# Fri3D_IRA_ESP32.net
KiCad netlist of a schematic drawn in Altium Designer
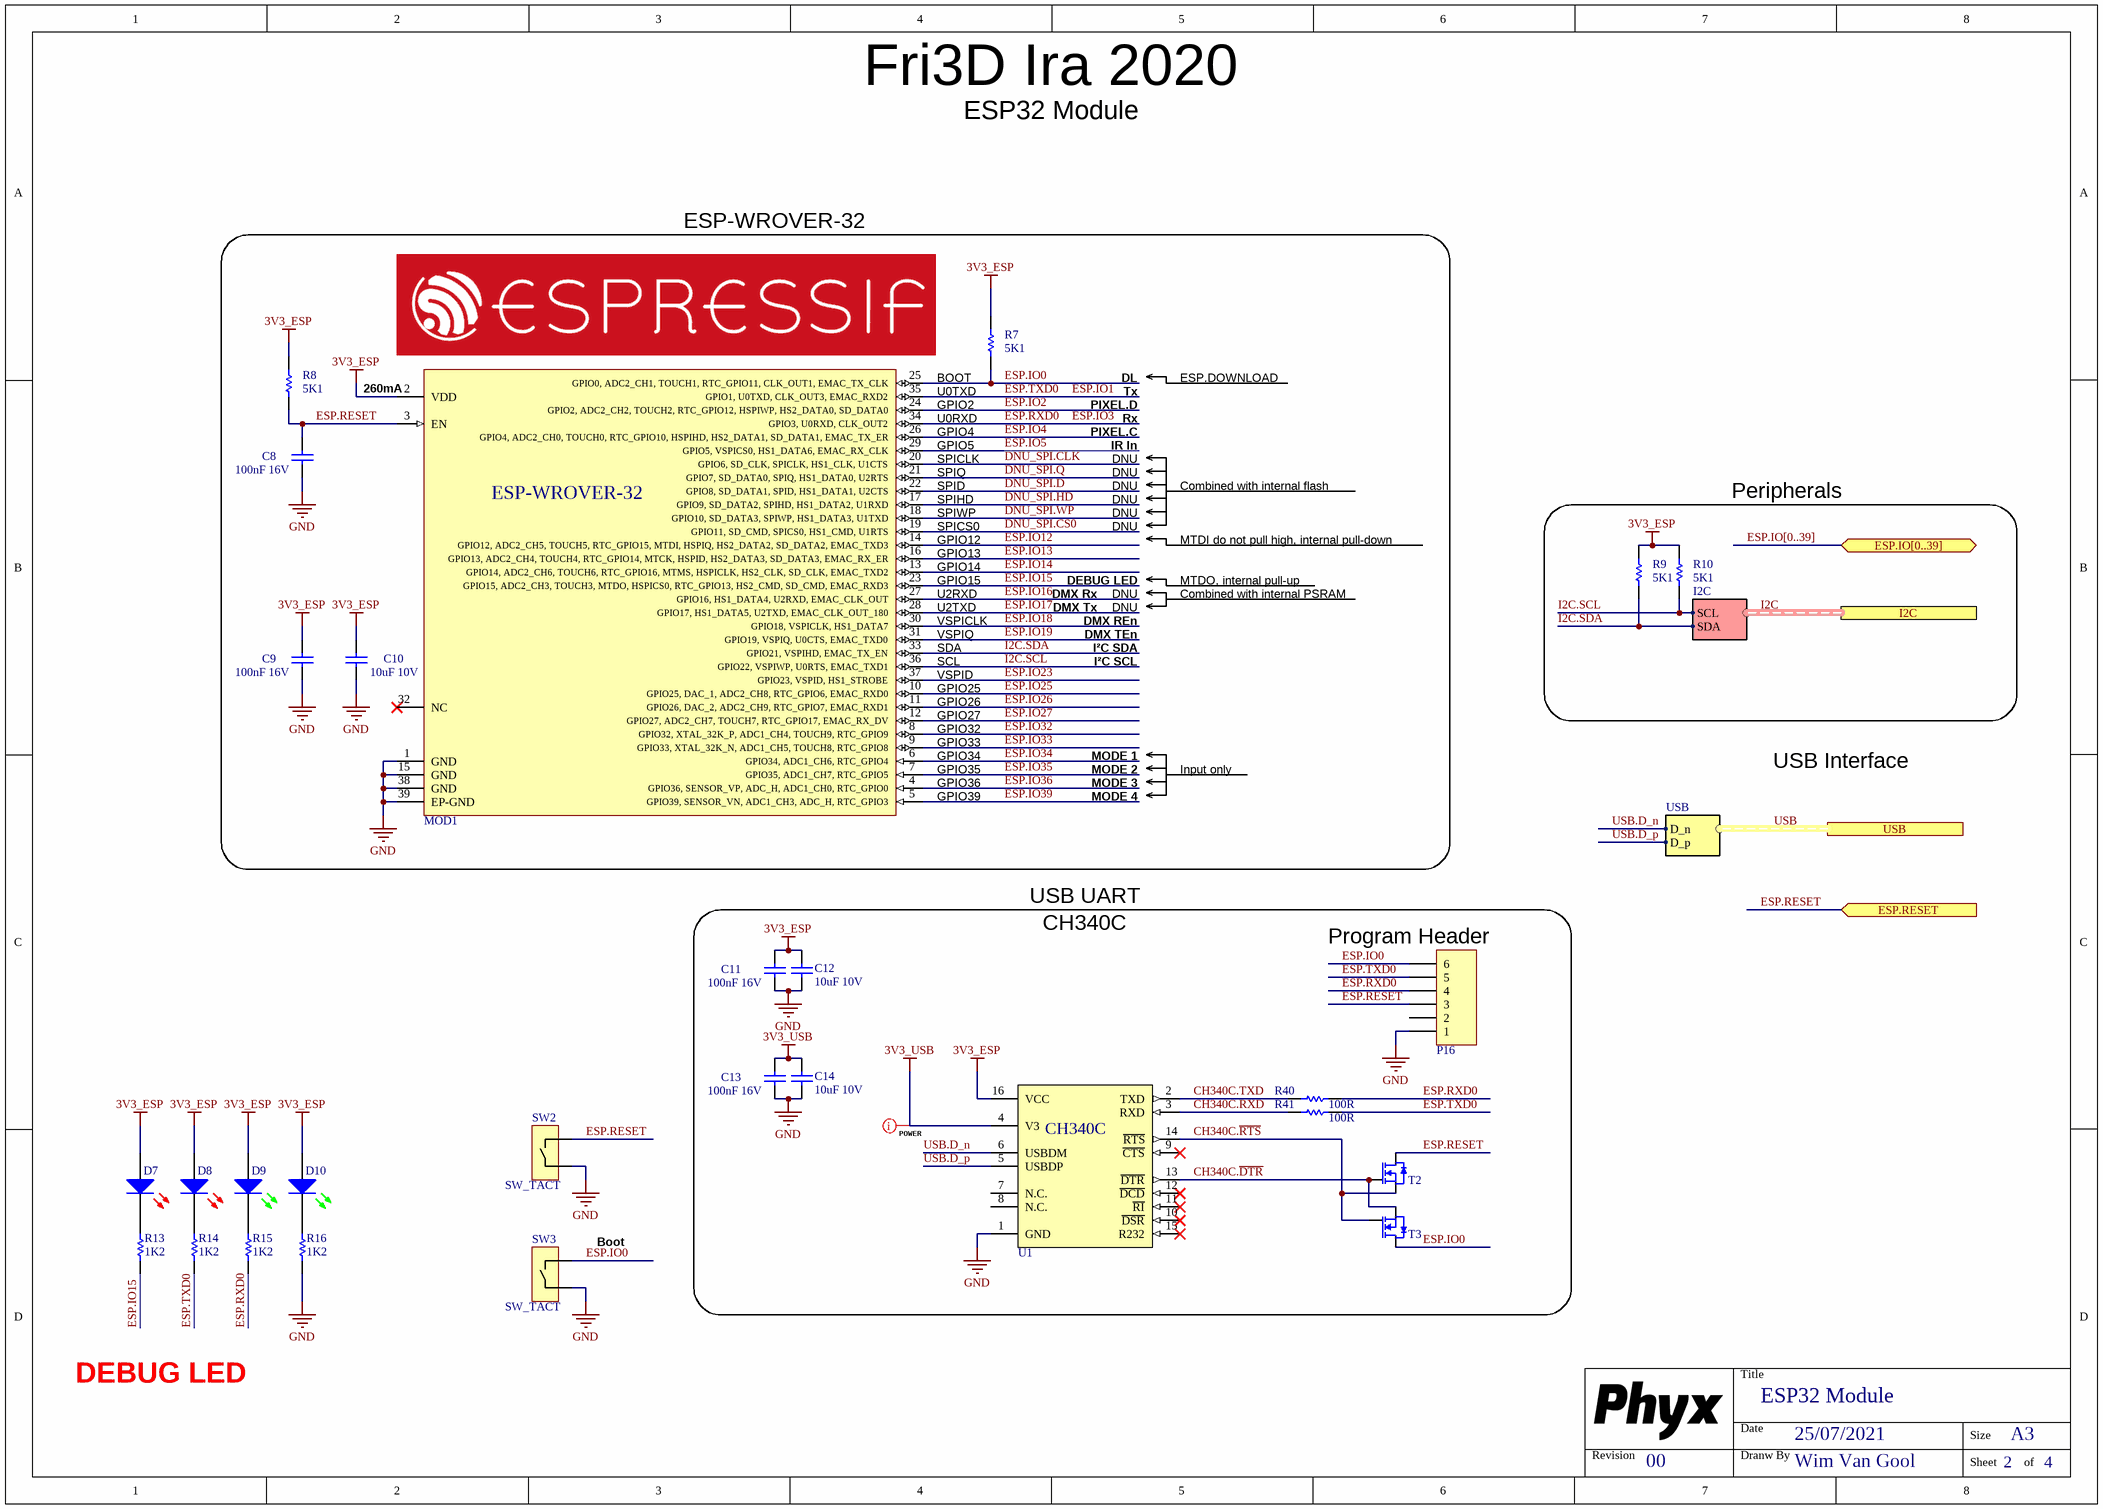
[diagram p0: Fri3D_IRA_ESP32.SchDoc]

(export (version "E")
  (design (tool "Eeschema 10.0.6"))
  (components
    (comp (ref "C8")
      (value "100nF 16V")
      (footprint "C0603_N")
      (description "Capacitor Ceramic")
      (libsource (lib "Phyx_Components") (part "CAP_CERAMIC"))
    )
    (comp (ref "C9")
      (value "100nF 16V")
      (footprint "C0603_N")
      (description "Capacitor Ceramic")
      (libsource (lib "Phyx_Components") (part "CAP_CERAMIC"))
    )
    (comp (ref "C10")
      (value "10uF 10V")
      (footprint "C0805_N")
      (description "Capacitor Ceramic")
      (fields (field (name "Comment") "CAP_CERAMIC"))
      (libsource (lib "Phyx_Components") (part "CAP_CERAMIC"))
    )
    (comp (ref "C11")
      (value "100nF 16V")
      (footprint "C0603_N")
      (description "Capacitor Ceramic")
      (libsource (lib "Phyx_Components") (part "CAP_CERAMIC"))
    )
    (comp (ref "C12")
      (value "10uF 10V")
      (footprint "C0805_N")
      (description "Capacitor Ceramic")
      (fields (field (name "Comment") "CAP_CERAMIC"))
      (libsource (lib "Phyx_Components") (part "CAP_CERAMIC"))
    )
    (comp (ref "C13")
      (value "100nF 16V")
      (footprint "C0603_N")
      (description "Capacitor Ceramic")
      (libsource (lib "Phyx_Components") (part "CAP_CERAMIC"))
    )
    (comp (ref "C14")
      (value "10uF 10V")
      (footprint "C0805_N")
      (description "Capacitor Ceramic")
      (fields (field (name "Comment") "CAP_CERAMIC"))
      (libsource (lib "Phyx_Components") (part "CAP_CERAMIC"))
    )
    (comp (ref "D7")
      (value "Default 0805 Red LED")
      (footprint "LED_0805_RD")
      (description "=Description")
      (libsource (lib "Phyx_Components") (part "LED_RED"))
    )
    (comp (ref "D8")
      (value "Default 0805 Red LED")
      (footprint "LED_0805_RD")
      (description "=Description")
      (libsource (lib "Phyx_Components") (part "LED_RED"))
    )
    (comp (ref "D9")
      (value "Default 0805 Green LED")
      (footprint "LED_0805_GR")
      (description "=Description")
      (libsource (lib "Phyx_Components") (part "LED_GREEN"))
    )
    (comp (ref "D10")
      (value "Default 0805 Green LED")
      (footprint "LED_0805_GR")
      (description "=Description")
      (libsource (lib "Phyx_Components") (part "LED_GREEN"))
    )
    (comp (ref "MOD1")
      (value "ESP-32 based ESP-WROVER-32")
      (footprint "ESP-WROVER-32")
      (description "WiFi # MOD ESP-WROVER-32")
      (libsource (lib "Phyx_Components") (part "ESP-WROVER-32"))
    )
    (comp (ref "P16")
      (value "Header 6")
      (footprint "HDR1X6")
      (libsource (lib "Phyx_Components") (part "Header 6"))
    )
    (comp (ref "R7")
      (value "5K1")
      (footprint "R0603_N")
      (fields (field (name "Comment") "RESISTOR"))
      (libsource (lib "Phyx_Components") (part "RESISTOR"))
    )
    (comp (ref "R8")
      (value "5K1")
      (footprint "R0603_N")
      (fields (field (name "Comment") "RESISTOR"))
      (libsource (lib "Phyx_Components") (part "RESISTOR"))
    )
    (comp (ref "R9")
      (value "5K1")
      (footprint "R0603_N")
      (fields (field (name "Comment") "RESISTOR"))
      (libsource (lib "Phyx_Components") (part "RESISTOR"))
    )
    (comp (ref "R10")
      (value "5K1")
      (footprint "R0603_N")
      (fields (field (name "Comment") "RESISTOR"))
      (libsource (lib "Phyx_Components") (part "RESISTOR"))
    )
    (comp (ref "R13")
      (value "1K2")
      (footprint "R0603_N")
      (fields (field (name "Comment") "RESISTOR"))
      (libsource (lib "Phyx_Components") (part "RESISTOR"))
    )
    (comp (ref "R14")
      (value "1K2")
      (footprint "R0603_N")
      (fields (field (name "Comment") "RESISTOR"))
      (libsource (lib "Phyx_Components") (part "RESISTOR"))
    )
    (comp (ref "R15")
      (value "1K2")
      (footprint "R0603_N")
      (fields (field (name "Comment") "RESISTOR"))
      (libsource (lib "Phyx_Components") (part "RESISTOR"))
    )
    (comp (ref "R16")
      (value "1K2")
      (footprint "R0603_N")
      (fields (field (name "Comment") "RESISTOR"))
      (libsource (lib "Phyx_Components") (part "RESISTOR"))
    )
    (comp (ref "R40")
      (value "100R")
      (footprint "R0603_N")
      (fields (field (name "Comment") "RESISTOR"))
      (libsource (lib "Phyx_Components") (part "RESISTOR"))
    )
    (comp (ref "R41")
      (value "100R")
      (footprint "R0603_N")
      (fields (field (name "Comment") "RESISTOR"))
      (libsource (lib "Phyx_Components") (part "RESISTOR"))
    )
    (comp (ref "SW2")
      (value "SW_TACT")
      (footprint "WE_430181038816")
      (libsource (lib "Phyx_Components") (part "SW_TACT"))
    )
    (comp (ref "SW3")
      (value "SW_TACT")
      (footprint "WE_430181038816")
      (libsource (lib "Phyx_Components") (part "SW_TACT"))
    )
    (comp (ref "T2")
      (value "0.2A N-Ch MOSFET Vgs 3.2")
      (footprint "SOT23-3")
      (libsource (lib "Phyx_Components") (part "N_MOSFET_GSD"))
    )
    (comp (ref "T3")
      (value "0.2A N-Ch MOSFET Vgs 3.2")
      (footprint "SOT23-3")
      (libsource (lib "Phyx_Components") (part "N_MOSFET_GSD"))
    )
    (comp (ref "U1")
      (value "USB to full UART with internal crystal")
      (footprint "SOIC_N_16")
      (description "=Description")
      (libsource (lib "Phyx_Components") (part "CH340C"))
    )
  )
  (nets
    (net (code "19") (name "/CH340C.RXD") (class "Default")
      (node (ref "R41") (pin "1") (pinfunction "1_1") (pintype "passive"))
      (node (ref "U1") (pin "3") (pinfunction "RXD_3") (pintype "input"))
    )
    (net (code "20") (name "/CH340C.TXD") (class "Default")
      (node (ref "R40") (pin "1") (pinfunction "1_1") (pintype "passive"))
      (node (ref "U1") (pin "2") (pinfunction "TXD_2") (pintype "output"))
    )
    (net (code "21") (name "/CH340C.~{DTR}") (class "Default")
      (node (ref "T2") (pin "1") (pinfunction "G_1") (pintype "passive"))
      (node (ref "T3") (pin "2") (pinfunction "S_2") (pintype "passive"))
      (node (ref "U1") (pin "13") (pinfunction "~{DTR}_13") (pintype "output"))
    )
    (net (code "22") (name "/CH340C.~{RTS}") (class "Default")
      (node (ref "T2") (pin "2") (pinfunction "S_2") (pintype "passive"))
      (node (ref "T3") (pin "1") (pinfunction "G_1") (pintype "passive"))
      (node (ref "U1") (pin "14") (pinfunction "~{RTS}_14") (pintype "output"))
    )
    (net (code "23") (name "/DNU_SPI.CLK") (class "Default")
      (node (ref "MOD1") (pin "20") (pinfunction "GPIO6,_SD_CLK,_SPICLK,_HS1_CLK,_U1CTS_20") (pintype "bidirectional"))
    )
    (net (code "24") (name "/DNU_SPI.CS0") (class "Default")
      (node (ref "MOD1") (pin "19") (pinfunction "GPIO11,_SD_CMD,_SPICS0,_HS1_CMD,_U1RTS_19") (pintype "bidirectional"))
    )
    (net (code "25") (name "/DNU_SPI.D") (class "Default")
      (node (ref "MOD1") (pin "22") (pinfunction "GPIO8,_SD_DATA1,_SPID,_HS1_DATA1,_U2CTS_22") (pintype "bidirectional"))
    )
    (net (code "26") (name "/DNU_SPI.HD") (class "Default")
      (node (ref "MOD1") (pin "17") (pinfunction "GPIO9,_SD_DATA2,_SPIHD,_HS1_DATA2,_U1RXD_17") (pintype "bidirectional"))
    )
    (net (code "27") (name "/DNU_SPI.Q") (class "Default")
      (node (ref "MOD1") (pin "21") (pinfunction "GPIO7,_SD_DATA0,_SPIQ,_HS1_DATA0,_U2RTS_21") (pintype "bidirectional"))
    )
    (net (code "28") (name "/DNU_SPI.WP") (class "Default")
      (node (ref "MOD1") (pin "18") (pinfunction "GPIO10,_SD_DATA3,_SPIWP,_HS1_DATA3,_U1TXD_18") (pintype "bidirectional"))
    )
    (net (code "29") (name "/ESP.IO0") (class "Default")
      (node (ref "MOD1") (pin "25") (pinfunction "GPIO0,_ADC2_CH1,_TOUCH1,_RTC_GPIO11,_CLK_OUT1,_EMAC_TX_CLK_25") (pintype "bidirectional"))
      (node (ref "P16") (pin "6") (pinfunction "6_6") (pintype "passive"))
      (node (ref "R7") (pin "2") (pinfunction "2_2") (pintype "passive"))
      (node (ref "SW3") (pin "1") (pinfunction "1_1") (pintype "passive"))
      (node (ref "T3") (pin "3") (pinfunction "D_3") (pintype "passive"))
    )
    (net (code "30") (name "/ESP.IO1") (class "Default")
      (node (ref "MOD1") (pin "35") (pinfunction "GPIO1,_U0TXD,_CLK_OUT3,_EMAC_RXD2_35") (pintype "bidirectional"))
      (node (ref "P16") (pin "5") (pinfunction "5_5") (pintype "passive"))
      (node (ref "R14") (pin "2") (pinfunction "2_2") (pintype "passive"))
      (node (ref "R41") (pin "2") (pinfunction "2_2") (pintype "passive"))
    )
    (net (code "31") (name "/ESP.IO2") (class "Default")
      (node (ref "MOD1") (pin "24") (pinfunction "GPIO2,_ADC2_CH2,_TOUCH2,_RTC_GPIO12,_HSPIWP,_HS2_DATA0,_SD_DATA0_24") (pintype "bidirectional"))
    )
    (net (code "32") (name "/ESP.IO3") (class "Default")
      (node (ref "MOD1") (pin "34") (pinfunction "GPIO3,_U0RXD,_CLK_OUT2_34") (pintype "bidirectional"))
      (node (ref "P16") (pin "4") (pinfunction "4_4") (pintype "passive"))
      (node (ref "R15") (pin "2") (pinfunction "2_2") (pintype "passive"))
      (node (ref "R40") (pin "2") (pinfunction "2_2") (pintype "passive"))
    )
    (net (code "33") (name "/ESP.IO4") (class "Default")
      (node (ref "MOD1") (pin "26") (pinfunction "GPIO4,_ADC2_CH0,_TOUCH0,_RTC_GPIO10,_HSPIHD,_HS2_DATA1,_SD_DATA1,_EMAC_TX_ER_26") (pintype "bidirectional"))
    )
    (net (code "34") (name "/ESP.IO5") (class "Default")
      (node (ref "MOD1") (pin "29") (pinfunction "GPIO5,_VSPICS0,_HS1_DATA6,_EMAC_RX_CLK_29") (pintype "bidirectional"))
    )
    (net (code "35") (name "/ESP.IO12") (class "Default")
      (node (ref "MOD1") (pin "14") (pinfunction "GPIO12,_ADC2_CH5,_TOUCH5,_RTC_GPIO15,_MTDI,_HSPIQ,_HS2_DATA2,_SD_DATA2,_EMAC_TXD3_14") (pintype "bidirectional"))
    )
    (net (code "36") (name "/ESP.IO13") (class "Default")
      (node (ref "MOD1") (pin "16") (pinfunction "GPIO13,_ADC2_CH4,_TOUCH4,_RTC_GPIO14,_MTCK,_HSPID,_HS2_DATA3,_SD_DATA3,_EMAC_RX_ER_16") (pintype "bidirectional"))
    )
    (net (code "37") (name "/ESP.IO14") (class "Default")
      (node (ref "MOD1") (pin "13") (pinfunction "GPIO14,_ADC2_CH6,_TOUCH6,_RTC_GPIO16,_MTMS,_HSPICLK,_HS2_CLK,_SD_CLK,_EMAC_TXD2_13") (pintype "bidirectional"))
    )
    (net (code "38") (name "/ESP.IO15") (class "Default")
      (node (ref "MOD1") (pin "23") (pinfunction "GPIO15,_ADC2_CH3,_TOUCH3,_MTDO,_HSPICS0,_RTC_GPIO13,_HS2_CMD,_SD_CMD,_EMAC_RXD3_23") (pintype "bidirectional"))
      (node (ref "R13") (pin "2") (pinfunction "2_2") (pintype "passive"))
    )
    (net (code "39") (name "/ESP.IO16") (class "Default")
      (node (ref "MOD1") (pin "27") (pinfunction "GPIO16,_HS1_DATA4,_U2RXD,_EMAC_CLK_OUT_27") (pintype "bidirectional"))
    )
    (net (code "40") (name "/ESP.IO17") (class "Default")
      (node (ref "MOD1") (pin "28") (pinfunction "GPIO17,_HS1_DATA5,_U2TXD,_EMAC_CLK_OUT_180_28") (pintype "bidirectional"))
    )
    (net (code "41") (name "/ESP.IO18") (class "Default")
      (node (ref "MOD1") (pin "30") (pinfunction "GPIO18,_VSPICLK,_HS1_DATA7_30") (pintype "bidirectional"))
    )
    (net (code "42") (name "/ESP.IO19") (class "Default")
      (node (ref "MOD1") (pin "31") (pinfunction "GPIO19,_VSPIQ,_U0CTS,_EMAC_TXD0_31") (pintype "bidirectional"))
    )
    (net (code "43") (name "/ESP.IO23") (class "Default")
      (node (ref "MOD1") (pin "37") (pinfunction "GPIO23,_VSPID,_HS1_STROBE_37") (pintype "bidirectional"))
    )
    (net (code "44") (name "/ESP.IO25") (class "Default")
      (node (ref "MOD1") (pin "10") (pinfunction "GPIO25,_DAC_1,_ADC2_CH8,_RTC_GPIO6,_EMAC_RXD0_10") (pintype "bidirectional"))
    )
    (net (code "45") (name "/ESP.IO26") (class "Default")
      (node (ref "MOD1") (pin "11") (pinfunction "GPIO26,_DAC_2,_ADC2_CH9,_RTC_GPIO7,_EMAC_RXD1_11") (pintype "bidirectional"))
    )
    (net (code "46") (name "/ESP.IO27") (class "Default")
      (node (ref "MOD1") (pin "12") (pinfunction "GPIO27,_ADC2_CH7,_TOUCH7,_RTC_GPIO17,_EMAC_RX_DV_12") (pintype "bidirectional"))
    )
    (net (code "47") (name "/ESP.IO32") (class "Default")
      (node (ref "MOD1") (pin "8") (pinfunction "GPIO32,_XTAL_32K_P,_ADC1_CH4,_TOUCH9,_RTC_GPIO9_8") (pintype "bidirectional"))
    )
    (net (code "48") (name "/ESP.IO33") (class "Default")
      (node (ref "MOD1") (pin "9") (pinfunction "GPIO33,_XTAL_32K_N,_ADC1_CH5,_TOUCH8,_RTC_GPIO8_9") (pintype "bidirectional"))
    )
    (net (code "49") (name "/ESP.IO34") (class "Default")
      (node (ref "MOD1") (pin "6") (pinfunction "GPIO34,_ADC1_CH6,_RTC_GPIO4_6") (pintype "input"))
    )
    (net (code "50") (name "/ESP.IO35") (class "Default")
      (node (ref "MOD1") (pin "7") (pinfunction "GPIO35,_ADC1_CH7,_RTC_GPIO5_7") (pintype "input"))
    )
    (net (code "51") (name "/ESP.IO36") (class "Default")
      (node (ref "MOD1") (pin "4") (pinfunction "GPIO36,_SENSOR_VP,_ADC_H,_ADC1_CH0,_RTC_GPIO0_4") (pintype "input"))
    )
    (net (code "52") (name "/ESP.IO39") (class "Default")
      (node (ref "MOD1") (pin "5") (pinfunction "GPIO39,_SENSOR_VN,_ADC1_CH3,_ADC_H,_RTC_GPIO3_5") (pintype "input"))
    )
    (net (code "54") (name "/ESP.RESET") (class "Default")
      (node (ref "C8") (pin "1") (pinfunction "1_1") (pintype "passive"))
      (node (ref "MOD1") (pin "3") (pinfunction "EN_3") (pintype "input"))
      (node (ref "P16") (pin "3") (pinfunction "3_3") (pintype "passive"))
      (node (ref "R8") (pin "2") (pinfunction "2_2") (pintype "passive"))
      (node (ref "SW2") (pin "1") (pinfunction "1_1") (pintype "passive"))
      (node (ref "T2") (pin "3") (pinfunction "D_3") (pintype "passive"))
    )
    (net (code "55") (name "/I2C.SCL") (class "Default")
      (node (ref "MOD1") (pin "36") (pinfunction "GPIO22,_VSPIWP,_U0RTS,_EMAC_TXD1_36") (pintype "bidirectional"))
      (node (ref "R10") (pin "2") (pinfunction "2_2") (pintype "passive"))
    )
    (net (code "56") (name "/I2C.SDA") (class "Default")
      (node (ref "MOD1") (pin "33") (pinfunction "GPIO21,_VSPIHD,_EMAC_TX_EN_33") (pintype "bidirectional"))
      (node (ref "R9") (pin "2") (pinfunction "2_2") (pintype "passive"))
    )
    (net (code "58") (name "/USB.D_n") (class "Default")
      (node (ref "U1") (pin "6") (pinfunction "USBDM_6") (pintype "passive"))
    )
    (net (code "59") (name "/USB.D_p") (class "Default")
      (node (ref "U1") (pin "5") (pinfunction "USBDP_5") (pintype "passive"))
    )
    (net (code "61") (name "3V3_ESP") (class "Default")
      (node (ref "C10") (pin "1") (pinfunction "1_1") (pintype "passive"))
      (node (ref "C11") (pin "1") (pinfunction "1_1") (pintype "passive"))
      (node (ref "C12") (pin "2") (pinfunction "2_2") (pintype "passive"))
      (node (ref "C9") (pin "1") (pinfunction "1_1") (pintype "passive"))
      (node (ref "D10") (pin "1") (pinfunction "A_1") (pintype "passive"))
      (node (ref "D7") (pin "1") (pinfunction "A_1") (pintype "passive"))
      (node (ref "D8") (pin "1") (pinfunction "A_1") (pintype "passive"))
      (node (ref "D9") (pin "1") (pinfunction "A_1") (pintype "passive"))
      (node (ref "MOD1") (pin "2") (pinfunction "VDD_2") (pintype "power_in"))
      (node (ref "R10") (pin "1") (pinfunction "1_1") (pintype "passive"))
      (node (ref "R7") (pin "1") (pinfunction "1_1") (pintype "passive"))
      (node (ref "R8") (pin "1") (pinfunction "1_1") (pintype "passive"))
      (node (ref "R9") (pin "1") (pinfunction "1_1") (pintype "passive"))
      (node (ref "U1") (pin "16") (pinfunction "VCC_16") (pintype "power_in"))
    )
    (net (code "62") (name "3V3_USB") (class "Default")
      (node (ref "C13") (pin "1") (pinfunction "1_1") (pintype "passive"))
      (node (ref "C14") (pin "2") (pinfunction "2_2") (pintype "passive"))
      (node (ref "U1") (pin "4") (pinfunction "V3_4") (pintype "power_in"))
    )
    (net (code "63") (name "GND") (class "Default")
      (node (ref "C10") (pin "2") (pinfunction "2_2") (pintype "passive"))
      (node (ref "C11") (pin "2") (pinfunction "2_2") (pintype "passive"))
      (node (ref "C12") (pin "1") (pinfunction "1_1") (pintype "passive"))
      (node (ref "C13") (pin "2") (pinfunction "2_2") (pintype "passive"))
      (node (ref "C14") (pin "1") (pinfunction "1_1") (pintype "passive"))
      (node (ref "C8") (pin "2") (pinfunction "2_2") (pintype "passive"))
      (node (ref "C9") (pin "2") (pinfunction "2_2") (pintype "passive"))
      (node (ref "MOD1") (pin "1") (pinfunction "GND_1") (pintype "power_in"))
      (node (ref "MOD1") (pin "15") (pinfunction "GND_15") (pintype "power_in"))
      (node (ref "MOD1") (pin "38") (pinfunction "GND_38") (pintype "power_in"))
      (node (ref "MOD1") (pin "39") (pinfunction "EP-GND_39") (pintype "power_in"))
      (node (ref "P16") (pin "1") (pinfunction "1_1") (pintype "passive"))
      (node (ref "R16") (pin "2") (pinfunction "2_2") (pintype "passive"))
      (node (ref "SW2") (pin "2") (pinfunction "2_2") (pintype "passive"))
      (node (ref "SW3") (pin "2") (pinfunction "2_2") (pintype "passive"))
      (node (ref "U1") (pin "1") (pinfunction "GND_1") (pintype "power_in"))
    )
    (net (code "64") (name "Net-(D7-K)") (class "Default")
      (node (ref "D7") (pin "2") (pinfunction "K_2") (pintype "passive"))
      (node (ref "R13") (pin "1") (pinfunction "1_1") (pintype "passive"))
    )
    (net (code "65") (name "Net-(D8-K)") (class "Default")
      (node (ref "D8") (pin "2") (pinfunction "K_2") (pintype "passive"))
      (node (ref "R14") (pin "1") (pinfunction "1_1") (pintype "passive"))
    )
    (net (code "66") (name "Net-(D9-K)") (class "Default")
      (node (ref "D9") (pin "2") (pinfunction "K_2") (pintype "passive"))
      (node (ref "R15") (pin "1") (pinfunction "1_1") (pintype "passive"))
    )
    (net (code "67") (name "Net-(D10-K)") (class "Default")
      (node (ref "D10") (pin "2") (pinfunction "K_2") (pintype "passive"))
      (node (ref "R16") (pin "1") (pinfunction "1_1") (pintype "passive"))
    )
    (net (code "68") (name "unconnected-(MOD1-NC-Pad32)") (class "Default")
      (node (ref "MOD1") (pin "32") (pinfunction "NC_32") (pintype "passive+no_connect"))
    )
    (net (code "69") (name "unconnected-(P16-Pad2)") (class "Default")
      (node (ref "P16") (pin "2") (pinfunction "2_2") (pintype "passive"))
    )
    (net (code "70") (name "unconnected-(U1-N.C.-Pad7)") (class "Default")
      (node (ref "U1") (pin "7") (pinfunction "N.C._7") (pintype "passive"))
    )
    (net (code "71") (name "unconnected-(U1-N.C.-Pad8)") (class "Default")
      (node (ref "U1") (pin "8") (pinfunction "N.C._8") (pintype "passive"))
    )
    (net (code "72") (name "unconnected-(U1-R232-Pad15)") (class "Default")
      (node (ref "U1") (pin "15") (pinfunction "R232_15") (pintype "input+no_connect"))
    )
    (net (code "73") (name "unconnected-(U1-~{CTS}-Pad9)") (class "Default")
      (node (ref "U1") (pin "9") (pinfunction "~{CTS}_9") (pintype "input+no_connect"))
    )
    (net (code "74") (name "unconnected-(U1-~{DCD}-Pad12)") (class "Default")
      (node (ref "U1") (pin "12") (pinfunction "~{DCD}_12") (pintype "input+no_connect"))
    )
    (net (code "75") (name "unconnected-(U1-~{DSR}-Pad10)") (class "Default")
      (node (ref "U1") (pin "10") (pinfunction "~{DSR}_10") (pintype "input+no_connect"))
    )
    (net (code "76") (name "unconnected-(U1-~{RI}-Pad11)") (class "Default")
      (node (ref "U1") (pin "11") (pinfunction "~{RI}_11") (pintype "input+no_connect"))
    )
  )
)
